# Power_Supply.net
KiCad netlist of a schematic drawn in Altium Designer
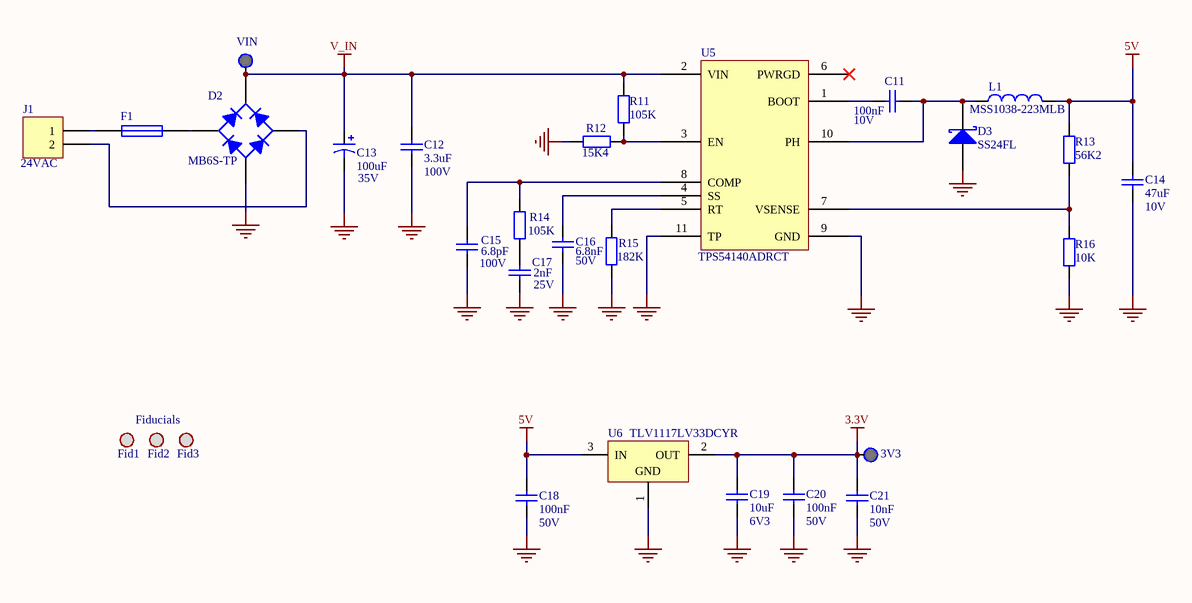
[diagram p0: Power Supply.SchDoc]

(export (version "E")
  (design (tool "Eeschema 10.0.6"))
  (components
    (comp (ref "3V3")
      (value "Test Point")
      (footprint "TP")
      (fields (field (name "PART NUMBER") "MIS-000000003"))
      (libsource (lib "ESP32-Relay-Module") (part "TP"))
    )
    (comp (ref "C11")
      (value "Capacitor")
      (footprint "CAPC1608N")
      (fields
        (field (name "PART NUMBER") "CAP-000000005")
        (field (name "VALUE 1") "100nF")
        (field (name "VALUE 2") "10V")
      )
      (libsource (lib "ESP32-Relay-Module") (part "Capacitor"))
    )
    (comp (ref "C12")
      (value "Capacitor")
      (footprint "CAPC3216N")
      (fields
        (field (name "PART NUMBER") "CAP-000000009")
        (field (name "VALUE 1") "3.3uF")
        (field (name "VALUE 2") "100V")
      )
      (libsource (lib "ESP32-Relay-Module") (part "Capacitor"))
    )
    (comp (ref "C13")
      (value "Polarized Capacitor")
      (footprint "ECAP_SMD_6.3")
      (fields
        (field (name "PART NUMBER") "CAP-000000001")
        (field (name "VALUE 1") "100uF")
        (field (name "VALUE 2") "35V")
      )
      (libsource (lib "ESP32-Relay-Module") (part "CPolarized"))
    )
    (comp (ref "C14")
      (value "Capacitor")
      (footprint "CAPC2012N")
      (fields
        (field (name "PART NUMBER") "CAP-000000004")
        (field (name "VALUE 1") "47uF")
        (field (name "VALUE 2") "10V")
      )
      (libsource (lib "ESP32-Relay-Module") (part "Capacitor"))
    )
    (comp (ref "C15")
      (value "Capacitor")
      (footprint "CAPC1608N")
      (fields
        (field (name "PART NUMBER") "CAP-000000008")
        (field (name "VALUE 1") "6.8pF")
        (field (name "VALUE 2") "100V")
      )
      (libsource (lib "ESP32-Relay-Module") (part "Capacitor"))
    )
    (comp (ref "C16")
      (value "Capacitor")
      (footprint "CAPC1608N")
      (fields
        (field (name "PART NUMBER") "CAP-000000006")
        (field (name "VALUE 1") "6.8nF")
        (field (name "VALUE 2") "50V")
      )
      (libsource (lib "ESP32-Relay-Module") (part "Capacitor"))
    )
    (comp (ref "C17")
      (value "Capacitor")
      (footprint "CAPC2012N")
      (fields
        (field (name "PART NUMBER") "CAP-000000007")
        (field (name "VALUE 1") "2nF")
        (field (name "VALUE 2") "25V")
      )
      (libsource (lib "ESP32-Relay-Module") (part "Capacitor"))
    )
    (comp (ref "C18")
      (value "Capacitor")
      (footprint "CAPC1608N")
      (fields
        (field (name "PART NUMBER") "CAP-000000002")
        (field (name "VALUE 1") "100nF")
        (field (name "VALUE 2") "50V")
      )
      (libsource (lib "ESP32-Relay-Module") (part "Capacitor"))
    )
    (comp (ref "C19")
      (value "Capacitor")
      (footprint "CAPC2012N")
      (fields
        (field (name "PART NUMBER") "CAP-000000001")
        (field (name "VALUE 1") "10uF")
        (field (name "VALUE 2") "6V3")
      )
      (libsource (lib "ESP32-Relay-Module") (part "Capacitor"))
    )
    (comp (ref "C20")
      (value "Capacitor")
      (footprint "CAPC1608N")
      (fields
        (field (name "PART NUMBER") "CAP-000000002")
        (field (name "VALUE 1") "100nF")
        (field (name "VALUE 2") "50V")
      )
      (libsource (lib "ESP32-Relay-Module") (part "Capacitor"))
    )
    (comp (ref "C21")
      (value "Capacitor")
      (footprint "CAPC1608N")
      (fields
        (field (name "PART NUMBER") "CAP-000000003")
        (field (name "VALUE 1") "10nF")
        (field (name "VALUE 2") "50V")
      )
      (libsource (lib "ESP32-Relay-Module") (part "Capacitor"))
    )
    (comp (ref "D2")
      (value "MB6S-TP")
      (footprint "MB6S")
      (fields (field (name "PART NUMBER") "DIB-000000001"))
      (libsource (lib "ESP32-Relay-Module") (part "DBridge"))
    )
    (comp (ref "D3")
      (value "SS24FL")
      (footprint "SOD-123F")
      (fields (field (name "PART NUMBER") "DIS-000000002"))
      (libsource (lib "ESP32-Relay-Module") (part "DSchottky"))
    )
    (comp (ref "F1")
      (value "0452.500NRL")
      (footprint "Fuse_NANO2")
      (fields (field (name "PART NUMBER") "FUS-000000002"))
      (libsource (lib "ESP32-Relay-Module") (part "Fuse"))
    )
    (comp (ref "Fid1")
      (value "Fiducial")
      (footprint "FIDUCIAL-1MM")
      (fields (field (name "PART NUMBER") "MIS-000000004"))
      (libsource (lib "ESP32-Relay-Module") (part "Fiducial"))
    )
    (comp (ref "Fid2")
      (value "Fiducial")
      (footprint "FIDUCIAL-1MM")
      (fields (field (name "PART NUMBER") "MIS-000000004"))
      (libsource (lib "ESP32-Relay-Module") (part "Fiducial"))
    )
    (comp (ref "Fid3")
      (value "Fiducial")
      (footprint "FIDUCIAL-1MM")
      (fields (field (name "PART NUMBER") "MIS-000000004"))
      (libsource (lib "ESP32-Relay-Module") (part "Fiducial"))
    )
    (comp (ref "J1")
      (value "24VAC")
      (footprint "CUI_TB007-508-02BE")
      (fields (field (name "PART NUMBER") "CON-000000001"))
      (libsource (lib "ESP32-Relay-Module") (part "Header 2"))
    )
    (comp (ref "L1")
      (value "MSS1038-223MLB")
      (footprint "MSS1038")
      (fields (field (name "PART NUMBER") "IND-000000001"))
      (libsource (lib "ESP32-Relay-Module") (part "Inductor"))
    )
    (comp (ref "R11")
      (value "Resistor")
      (footprint "RESC1608N")
      (fields (field (name "PART NUMBER") "RES-000000003") (field (name "VALUE 1") "105K"))
      (libsource (lib "ESP32-Relay-Module") (part "Resistor"))
    )
    (comp (ref "R12")
      (value "Resistor")
      (footprint "RESC1608N")
      (fields (field (name "PART NUMBER") "RES-000000002") (field (name "VALUE 1") "15K4"))
      (libsource (lib "") (part "Resistor_1"))
    )
    (comp (ref "R13")
      (value "Resistor")
      (footprint "RESC1608N")
      (fields (field (name "PART NUMBER") "RES-000000005") (field (name "VALUE 1") "56K2"))
      (libsource (lib "ESP32-Relay-Module") (part "Resistor"))
    )
    (comp (ref "R14")
      (value "Resistor")
      (footprint "RESC1608N")
      (fields (field (name "PART NUMBER") "RES-000000003") (field (name "VALUE 1") "105K"))
      (libsource (lib "ESP32-Relay-Module") (part "Resistor"))
    )
    (comp (ref "R15")
      (value "Resistor")
      (footprint "RESC1608N")
      (fields (field (name "PART NUMBER") "RES-000000004") (field (name "VALUE 1") "182K"))
      (libsource (lib "ESP32-Relay-Module") (part "Resistor"))
    )
    (comp (ref "R16")
      (value "Resistor")
      (footprint "RESC1608N")
      (fields (field (name "PART NUMBER") "RES-000000001") (field (name "VALUE 1") "10K"))
      (libsource (lib "ESP32-Relay-Module") (part "Resistor"))
    )
    (comp (ref "U5")
      (value "TPS54140ADRCT")
      (footprint "VSON-10")
      (fields (field (name "PART NUMBER") "ICP-000000006"))
      (libsource (lib "ESP32-Relay-Module") (part "TPS54140A"))
    )
    (comp (ref "U6")
      (value "TLV1117LV33DCYR")
      (footprint "SOT223")
      (fields (field (name "PART NUMBER") "VRG-000000001"))
      (libsource (lib "ESP32-Relay-Module") (part "TLV1117"))
    )
    (comp (ref "VIN")
      (value "Test Point")
      (footprint "TP")
      (fields (field (name "PART NUMBER") "MIS-000000003"))
      (libsource (lib "ESP32-Relay-Module") (part "TP"))
    )
  )
  (nets
    (net (code "1") (name "3.3V") (class "Default")
      (node (ref "3V3") (pin "1") (pinfunction "1_1") (pintype "passive"))
      (node (ref "C19") (pin "2") (pinfunction "2_2") (pintype "passive"))
      (node (ref "C20") (pin "2") (pinfunction "2_2") (pintype "passive"))
      (node (ref "C21") (pin "2") (pinfunction "2_2") (pintype "passive"))
      (node (ref "U6") (pin "2") (pinfunction "OUT_2") (pintype "power_in"))
    )
    (net (code "2") (name "5V") (class "Default")
      (node (ref "C14") (pin "2") (pinfunction "2_2") (pintype "passive"))
      (node (ref "C18") (pin "2") (pinfunction "2_2") (pintype "passive"))
      (node (ref "L1") (pin "2") (pinfunction "2_2") (pintype "passive"))
      (node (ref "R13") (pin "2") (pinfunction "2_2") (pintype "passive"))
      (node (ref "U6") (pin "3") (pinfunction "IN_3") (pintype "power_in"))
    )
    (net (code "3") (name "GND") (class "Default")
      (node (ref "C12") (pin "1") (pinfunction "1_1") (pintype "passive"))
      (node (ref "C13") (pin "2") (pinfunction "2_2") (pintype "passive"))
      (node (ref "C14") (pin "1") (pinfunction "1_1") (pintype "passive"))
      (node (ref "C15") (pin "1") (pinfunction "1_1") (pintype "passive"))
      (node (ref "C16") (pin "1") (pinfunction "1_1") (pintype "passive"))
      (node (ref "C17") (pin "1") (pinfunction "1_1") (pintype "passive"))
      (node (ref "C18") (pin "1") (pinfunction "1_1") (pintype "passive"))
      (node (ref "C19") (pin "1") (pinfunction "1_1") (pintype "passive"))
      (node (ref "C20") (pin "1") (pinfunction "1_1") (pintype "passive"))
      (node (ref "C21") (pin "1") (pinfunction "1_1") (pintype "passive"))
      (node (ref "D2") (pin "3") (pinfunction "A_3") (pintype "passive"))
      (node (ref "D3") (pin "1") (pinfunction "A_1") (pintype "passive"))
      (node (ref "R12") (pin "1") (pinfunction "1_1") (pintype "passive"))
      (node (ref "R15") (pin "1") (pinfunction "1_1") (pintype "passive"))
      (node (ref "R16") (pin "1") (pinfunction "1_1") (pintype "passive"))
      (node (ref "U5") (pin "11") (pinfunction "TP_11") (pintype "passive"))
      (node (ref "U5") (pin "9") (pinfunction "GND_9") (pintype "passive"))
      (node (ref "U6") (pin "1") (pinfunction "GND_1") (pintype "power_in"))
    )
    (net (code "4") (name "Net-(C17-Pad2)") (class "Default")
      (node (ref "C17") (pin "2") (pinfunction "2_2") (pintype "passive"))
      (node (ref "R14") (pin "1") (pinfunction "1_1") (pintype "passive"))
    )
    (net (code "5") (name "Net-(D2-C-Pad2)") (class "Default")
      (node (ref "D2") (pin "2") (pinfunction "C_2") (pintype "passive"))
      (node (ref "J1") (pin "2") (pinfunction "2_2") (pintype "passive"))
    )
    (net (code "6") (name "Net-(D2-C-Pad4)") (class "Default")
      (node (ref "D2") (pin "4") (pinfunction "C_4") (pintype "passive"))
      (node (ref "F1") (pin "2") (pinfunction "2_2") (pintype "passive"))
    )
    (net (code "7") (name "Net-(D3-K)") (class "Default")
      (node (ref "C11") (pin "2") (pinfunction "2_2") (pintype "passive"))
      (node (ref "D3") (pin "2") (pinfunction "K_2") (pintype "passive"))
      (node (ref "L1") (pin "1") (pinfunction "1_1") (pintype "passive"))
      (node (ref "U5") (pin "10") (pinfunction "PH_10") (pintype "passive"))
    )
    (net (code "8") (name "Net-(F1-Pad1)") (class "Default")
      (node (ref "F1") (pin "1") (pinfunction "1_1") (pintype "passive"))
      (node (ref "J1") (pin "1") (pinfunction "1_1") (pintype "passive"))
    )
    (net (code "9") (name "Net-(U5-BOOT)") (class "Default")
      (node (ref "C11") (pin "1") (pinfunction "1_1") (pintype "passive"))
      (node (ref "U5") (pin "1") (pinfunction "BOOT_1") (pintype "passive"))
    )
    (net (code "10") (name "Net-(U5-COMP)") (class "Default")
      (node (ref "C15") (pin "2") (pinfunction "2_2") (pintype "passive"))
      (node (ref "R14") (pin "2") (pinfunction "2_2") (pintype "passive"))
      (node (ref "U5") (pin "8") (pinfunction "COMP_8") (pintype "passive"))
    )
    (net (code "11") (name "Net-(U5-EN)") (class "Default")
      (node (ref "R11") (pin "1") (pinfunction "1_1") (pintype "passive"))
      (node (ref "R12") (pin "2") (pinfunction "2_2") (pintype "passive"))
      (node (ref "U5") (pin "3") (pinfunction "EN_3") (pintype "passive"))
    )
    (net (code "12") (name "Net-(U5-RT)") (class "Default")
      (node (ref "R15") (pin "2") (pinfunction "2_2") (pintype "passive"))
      (node (ref "U5") (pin "5") (pinfunction "RT_5") (pintype "passive"))
    )
    (net (code "13") (name "Net-(U5-SS)") (class "Default")
      (node (ref "C16") (pin "2") (pinfunction "2_2") (pintype "passive"))
      (node (ref "U5") (pin "4") (pinfunction "SS_4") (pintype "passive"))
    )
    (net (code "14") (name "Net-(U5-VSENSE)") (class "Default")
      (node (ref "R13") (pin "1") (pinfunction "1_1") (pintype "passive"))
      (node (ref "R16") (pin "2") (pinfunction "2_2") (pintype "passive"))
      (node (ref "U5") (pin "7") (pinfunction "VSENSE_7") (pintype "passive"))
    )
    (net (code "15") (name "V_IN") (class "Default")
      (node (ref "C12") (pin "2") (pinfunction "2_2") (pintype "passive"))
      (node (ref "C13") (pin "1") (pinfunction "1_1") (pintype "passive"))
      (node (ref "D2") (pin "1") (pinfunction "K_1") (pintype "passive"))
      (node (ref "R11") (pin "2") (pinfunction "2_2") (pintype "passive"))
      (node (ref "U5") (pin "2") (pinfunction "VIN_2") (pintype "passive"))
      (node (ref "VIN") (pin "1") (pinfunction "1_1") (pintype "passive"))
    )
    (net (code "16") (name "unconnected-(U5-PWRGD-Pad6)") (class "Default")
      (node (ref "U5") (pin "6") (pinfunction "PWRGD_6") (pintype "passive+no_connect"))
    )
  )
)
